# Bluetooth.net
KiCad netlist of a schematic drawn in Altium Designer
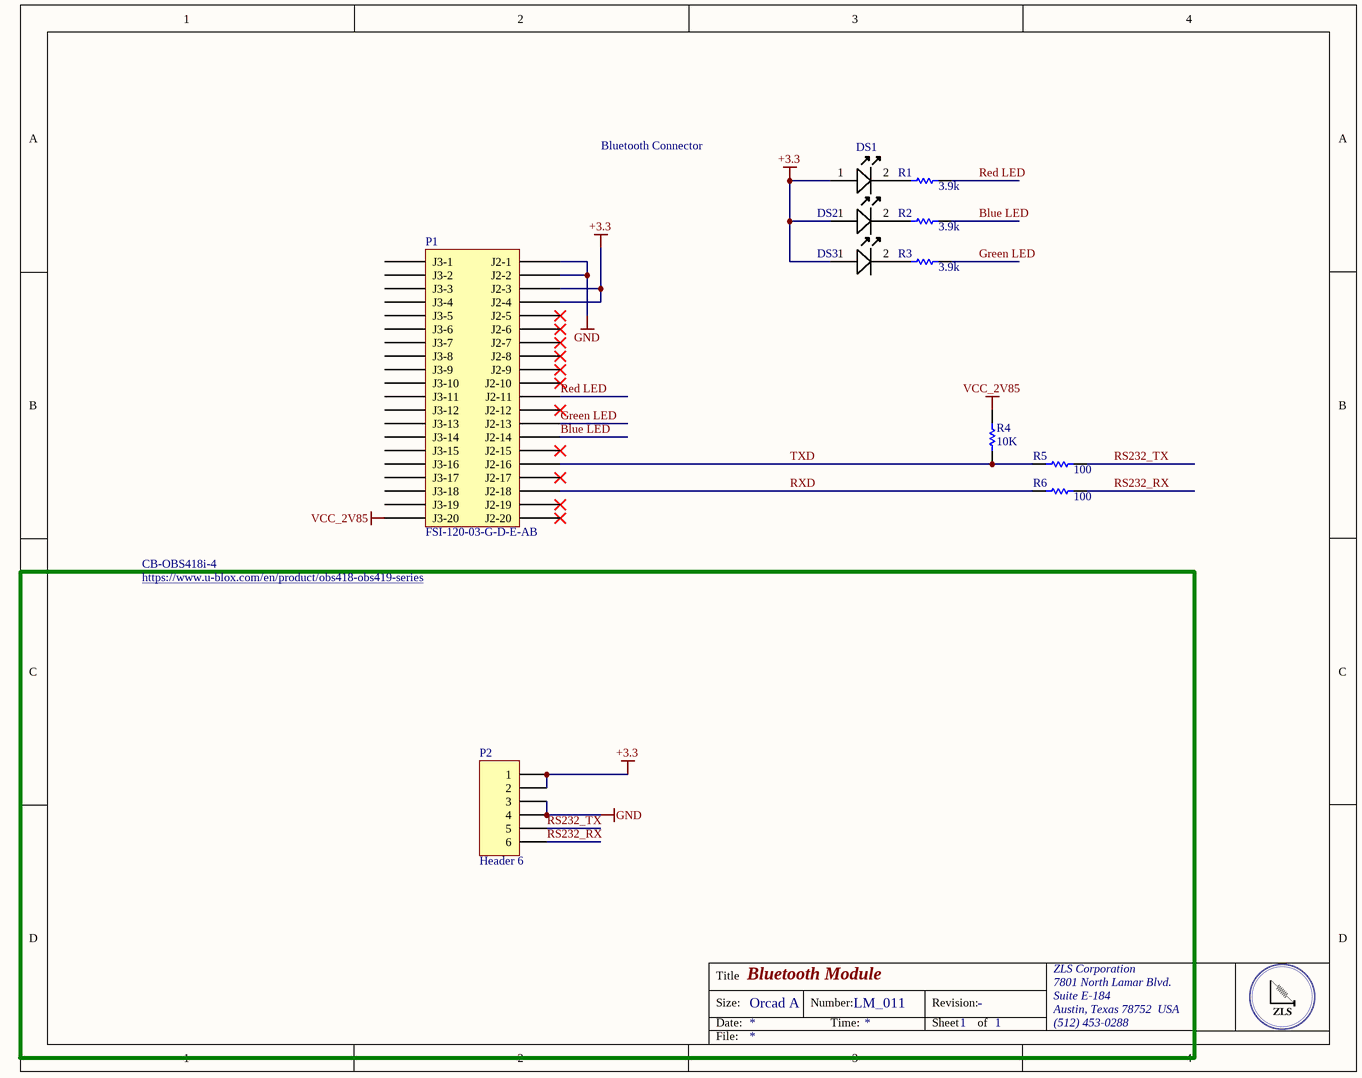
[diagram p0: Bluetooth.SchDoc]

(export (version "E")
  (design (tool "Eeschema 10.0.6"))
  (components
    (comp (ref "DS1")
      (value "Lite-On LTST-S220KGKT Green LED, 571 nm 2012 (0805) Side View, Rectangle Lens SMD package")
      (footprint "0805C_L")
      (fields
        (field (name "MANUFACTURER") "Vishay / Lite-On")
        (field (name "MANUFACTURER PART NUMBER") "LTST-S220KGKT")
      )
      (libsource (lib "*") (part "LED A/K"))
    )
    (comp (ref "DS2")
      (value "Lite-On LTST-S220KGKT Green LED, 571 nm 2012 (0805) Side View, Rectangle Lens SMD package")
      (footprint "0805C_L")
      (fields
        (field (name "MANUFACTURER") "Vishay / Lite-On")
        (field (name "MANUFACTURER PART NUMBER") "LTST-S220KGKT")
      )
      (libsource (lib "*") (part "LED A/K"))
    )
    (comp (ref "DS3")
      (value "Lite-On LTST-S220KGKT Green LED, 571 nm 2012 (0805) Side View, Rectangle Lens SMD package")
      (footprint "0805C_L")
      (fields
        (field (name "MANUFACTURER") "Vishay / Lite-On")
        (field (name "MANUFACTURER PART NUMBER") "LTST-S220KGKT")
      )
      (libsource (lib "*") (part "LED A/K"))
    )
    (comp (ref "P1")
      (value "FSI-120-03-G-D-E-AB")
      (footprint "FSI-120-03-G-D-E-AB")
      (fields (field (name "SUPPLIER PART NUMBER 1") "FSI-120-03-G-D-E-AB"))
      (libsource (lib "ZLS_Schematic_lib") (part "FSI-120-03-G-D-E-AB"))
    )
    (comp (ref "P2")
      (value "Header 6")
      (footprint "HDR1X6")
      (description "Header, 6-Pin")
      (fields (field (name "PUBLISHER") "Altium Limited"))
      (libsource (lib "Miscellaneous Connectors") (part "Header 6"))
    )
    (comp (ref "R1")
      (value "3.9k")
      (footprint "RESC0805(2012)_L")
      (description "2R55 0.125W 1% 0805 (2012 Metric)  SMD")
      (fields (field (name "TOLERANCE") "1 %") (field (name "POWER") "0.125 W"))
      (libsource (lib "Altium Content Vault") (part "CMP-1013-00215-1"))
    )
    (comp (ref "R2")
      (value "3.9k")
      (footprint "RESC0805(2012)_L")
      (description "2R55 0.125W 1% 0805 (2012 Metric)  SMD")
      (fields (field (name "TOLERANCE") "1 %") (field (name "POWER") "0.125 W"))
      (libsource (lib "Altium Content Vault") (part "CMP-1013-00215-1"))
    )
    (comp (ref "R3")
      (value "3.9k")
      (footprint "RESC0805(2012)_L")
      (description "2R55 0.125W 1% 0805 (2012 Metric)  SMD")
      (fields (field (name "TOLERANCE") "1 %") (field (name "POWER") "0.125 W"))
      (libsource (lib "Altium Content Vault") (part "CMP-1013-00215-1"))
    )
    (comp (ref "R4")
      (value "10K")
      (footprint "RESC0805(2012)_L")
      (description "2R55 0.125W 1% 0805 (2012 Metric)  SMD")
      (fields (field (name "TOLERANCE") "1 %") (field (name "POWER") "0.125 W"))
      (libsource (lib "Altium Content Vault") (part "CMP-1013-00215-1"))
    )
    (comp (ref "R5")
      (value "100")
      (footprint "RESC0805(2012)_L")
      (description "2R55 0.125W 1% 0805 (2012 Metric)  SMD")
      (fields (field (name "TOLERANCE") "1 %") (field (name "POWER") "0.125 W"))
      (libsource (lib "Altium Content Vault") (part "CMP-1013-00215-1"))
    )
    (comp (ref "R6")
      (value "100")
      (footprint "RESC0805(2012)_L")
      (description "2R55 0.125W 1% 0805 (2012 Metric)  SMD")
      (fields (field (name "TOLERANCE") "1 %") (field (name "POWER") "0.125 W"))
      (libsource (lib "Altium Content Vault") (part "CMP-1013-00215-1"))
    )
  )
  (nets
    (net (code "1") (name "+3.3") (class "Default")
      (node (ref "DS1") (pin "1") (pinfunction "A_1") (pintype "passive"))
      (node (ref "DS2") (pin "1") (pinfunction "A_1") (pintype "passive"))
      (node (ref "DS3") (pin "1") (pinfunction "A_1") (pintype "passive"))
      (node (ref "P1") (pin "J2-3") (pinfunction "J2-3_J2-3") (pintype "passive"))
      (node (ref "P1") (pin "J2-4") (pinfunction "J2-4_J2-4") (pintype "passive"))
      (node (ref "P2") (pin "1") (pinfunction "1_1") (pintype "passive"))
      (node (ref "P2") (pin "2") (pinfunction "2_2") (pintype "passive"))
    )
    (net (code "2") (name "/Blue LED") (class "Default")
      (node (ref "P1") (pin "J2-14") (pinfunction "J2-14_J2-14") (pintype "passive"))
      (node (ref "R2") (pin "1") (pinfunction "1_1") (pintype "passive"))
    )
    (net (code "3") (name "/Green LED") (class "Default")
      (node (ref "P1") (pin "J2-13") (pinfunction "J2-13_J2-13") (pintype "passive"))
      (node (ref "R3") (pin "1") (pinfunction "1_1") (pintype "passive"))
    )
    (net (code "4") (name "/RS232_RX") (class "Default")
      (node (ref "P2") (pin "6") (pinfunction "6_6") (pintype "passive"))
      (node (ref "R6") (pin "1") (pinfunction "1_1") (pintype "passive"))
    )
    (net (code "5") (name "/RS232_TX") (class "Default")
      (node (ref "P2") (pin "5") (pinfunction "5_5") (pintype "passive"))
      (node (ref "R5") (pin "1") (pinfunction "1_1") (pintype "passive"))
    )
    (net (code "6") (name "/RXD") (class "Default")
      (node (ref "P1") (pin "J2-18") (pinfunction "J2-18_J2-18") (pintype "passive"))
      (node (ref "R6") (pin "2") (pinfunction "2_2") (pintype "passive"))
    )
    (net (code "7") (name "/Red LED") (class "Default")
      (node (ref "P1") (pin "J2-11") (pinfunction "J2-11_J2-11") (pintype "passive"))
      (node (ref "R1") (pin "1") (pinfunction "1_1") (pintype "passive"))
    )
    (net (code "8") (name "/TXD") (class "Default")
      (node (ref "P1") (pin "J2-16") (pinfunction "J2-16_J2-16") (pintype "passive"))
      (node (ref "R4") (pin "2") (pinfunction "2_2") (pintype "passive"))
      (node (ref "R5") (pin "2") (pinfunction "2_2") (pintype "passive"))
    )
    (net (code "9") (name "GND") (class "Default")
      (node (ref "P1") (pin "J2-1") (pinfunction "J2-1_J2-1") (pintype "passive"))
      (node (ref "P1") (pin "J2-2") (pinfunction "J2-2_J2-2") (pintype "passive"))
      (node (ref "P2") (pin "3") (pinfunction "3_3") (pintype "passive"))
      (node (ref "P2") (pin "4") (pinfunction "4_4") (pintype "passive"))
    )
    (net (code "10") (name "Net-(DS1-K)") (class "Default")
      (node (ref "DS1") (pin "2") (pinfunction "K_2") (pintype "passive"))
      (node (ref "R1") (pin "2") (pinfunction "2_2") (pintype "passive"))
    )
    (net (code "11") (name "Net-(DS2-K)") (class "Default")
      (node (ref "DS2") (pin "2") (pinfunction "K_2") (pintype "passive"))
      (node (ref "R2") (pin "2") (pinfunction "2_2") (pintype "passive"))
    )
    (net (code "12") (name "Net-(DS3-K)") (class "Default")
      (node (ref "DS3") (pin "2") (pinfunction "K_2") (pintype "passive"))
      (node (ref "R3") (pin "2") (pinfunction "2_2") (pintype "passive"))
    )
    (net (code "13") (name "VCC_2V85") (class "Default")
      (node (ref "P1") (pin "J3-20") (pinfunction "J3-20_J3-20") (pintype "passive"))
      (node (ref "R4") (pin "1") (pinfunction "1_1") (pintype "passive"))
    )
    (net (code "14") (name "unconnected-(P1-PadJ2-5)") (class "Default")
      (node (ref "P1") (pin "J2-5") (pinfunction "J2-5_J2-5") (pintype "passive+no_connect"))
    )
    (net (code "15") (name "unconnected-(P1-PadJ2-6)") (class "Default")
      (node (ref "P1") (pin "J2-6") (pinfunction "J2-6_J2-6") (pintype "passive+no_connect"))
    )
    (net (code "16") (name "unconnected-(P1-PadJ2-7)") (class "Default")
      (node (ref "P1") (pin "J2-7") (pinfunction "J2-7_J2-7") (pintype "passive+no_connect"))
    )
    (net (code "17") (name "unconnected-(P1-PadJ2-8)") (class "Default")
      (node (ref "P1") (pin "J2-8") (pinfunction "J2-8_J2-8") (pintype "passive+no_connect"))
    )
    (net (code "18") (name "unconnected-(P1-PadJ2-9)") (class "Default")
      (node (ref "P1") (pin "J2-9") (pinfunction "J2-9_J2-9") (pintype "passive+no_connect"))
    )
    (net (code "19") (name "unconnected-(P1-PadJ2-10)") (class "Default")
      (node (ref "P1") (pin "J2-10") (pinfunction "J2-10_J2-10") (pintype "passive+no_connect"))
    )
    (net (code "20") (name "unconnected-(P1-PadJ2-12)") (class "Default")
      (node (ref "P1") (pin "J2-12") (pinfunction "J2-12_J2-12") (pintype "passive+no_connect"))
    )
    (net (code "21") (name "unconnected-(P1-PadJ2-15)") (class "Default")
      (node (ref "P1") (pin "J2-15") (pinfunction "J2-15_J2-15") (pintype "passive+no_connect"))
    )
    (net (code "22") (name "unconnected-(P1-PadJ2-17)") (class "Default")
      (node (ref "P1") (pin "J2-17") (pinfunction "J2-17_J2-17") (pintype "passive+no_connect"))
    )
    (net (code "23") (name "unconnected-(P1-PadJ2-19)") (class "Default")
      (node (ref "P1") (pin "J2-19") (pinfunction "J2-19_J2-19") (pintype "passive+no_connect"))
    )
    (net (code "24") (name "unconnected-(P1-PadJ2-20)") (class "Default")
      (node (ref "P1") (pin "J2-20") (pinfunction "J2-20_J2-20") (pintype "passive+no_connect"))
    )
    (net (code "25") (name "unconnected-(P1-PadJ3-1)") (class "Default")
      (node (ref "P1") (pin "J3-1") (pinfunction "J3-1_J3-1") (pintype "passive"))
    )
    (net (code "26") (name "unconnected-(P1-PadJ3-2)") (class "Default")
      (node (ref "P1") (pin "J3-2") (pinfunction "J3-2_J3-2") (pintype "passive"))
    )
    (net (code "27") (name "unconnected-(P1-PadJ3-3)") (class "Default")
      (node (ref "P1") (pin "J3-3") (pinfunction "J3-3_J3-3") (pintype "passive"))
    )
    (net (code "28") (name "unconnected-(P1-PadJ3-4)") (class "Default")
      (node (ref "P1") (pin "J3-4") (pinfunction "J3-4_J3-4") (pintype "passive"))
    )
    (net (code "29") (name "unconnected-(P1-PadJ3-5)") (class "Default")
      (node (ref "P1") (pin "J3-5") (pinfunction "J3-5_J3-5") (pintype "passive"))
    )
    (net (code "30") (name "unconnected-(P1-PadJ3-6)") (class "Default")
      (node (ref "P1") (pin "J3-6") (pinfunction "J3-6_J3-6") (pintype "passive"))
    )
    (net (code "31") (name "unconnected-(P1-PadJ3-7)") (class "Default")
      (node (ref "P1") (pin "J3-7") (pinfunction "J3-7_J3-7") (pintype "passive"))
    )
    (net (code "32") (name "unconnected-(P1-PadJ3-8)") (class "Default")
      (node (ref "P1") (pin "J3-8") (pinfunction "J3-8_J3-8") (pintype "passive"))
    )
    (net (code "33") (name "unconnected-(P1-PadJ3-9)") (class "Default")
      (node (ref "P1") (pin "J3-9") (pinfunction "J3-9_J3-9") (pintype "passive"))
    )
    (net (code "34") (name "unconnected-(P1-PadJ3-10)") (class "Default")
      (node (ref "P1") (pin "J3-10") (pinfunction "J3-10_J3-10") (pintype "passive"))
    )
    (net (code "35") (name "unconnected-(P1-PadJ3-11)") (class "Default")
      (node (ref "P1") (pin "J3-11") (pinfunction "J3-11_J3-11") (pintype "passive"))
    )
    (net (code "36") (name "unconnected-(P1-PadJ3-12)") (class "Default")
      (node (ref "P1") (pin "J3-12") (pinfunction "J3-12_J3-12") (pintype "passive"))
    )
    (net (code "37") (name "unconnected-(P1-PadJ3-13)") (class "Default")
      (node (ref "P1") (pin "J3-13") (pinfunction "J3-13_J3-13") (pintype "passive"))
    )
    (net (code "38") (name "unconnected-(P1-PadJ3-14)") (class "Default")
      (node (ref "P1") (pin "J3-14") (pinfunction "J3-14_J3-14") (pintype "passive"))
    )
    (net (code "39") (name "unconnected-(P1-PadJ3-15)") (class "Default")
      (node (ref "P1") (pin "J3-15") (pinfunction "J3-15_J3-15") (pintype "passive"))
    )
    (net (code "40") (name "unconnected-(P1-PadJ3-16)") (class "Default")
      (node (ref "P1") (pin "J3-16") (pinfunction "J3-16_J3-16") (pintype "passive"))
    )
    (net (code "41") (name "unconnected-(P1-PadJ3-17)") (class "Default")
      (node (ref "P1") (pin "J3-17") (pinfunction "J3-17_J3-17") (pintype "passive"))
    )
    (net (code "42") (name "unconnected-(P1-PadJ3-18)") (class "Default")
      (node (ref "P1") (pin "J3-18") (pinfunction "J3-18_J3-18") (pintype "passive"))
    )
    (net (code "43") (name "unconnected-(P1-PadJ3-19)") (class "Default")
      (node (ref "P1") (pin "J3-19") (pinfunction "J3-19_J3-19") (pintype "passive"))
    )
  )
)
